# axiom_beta_shield_debug.net
KiCad netlist of a schematic drawn in EAGLE
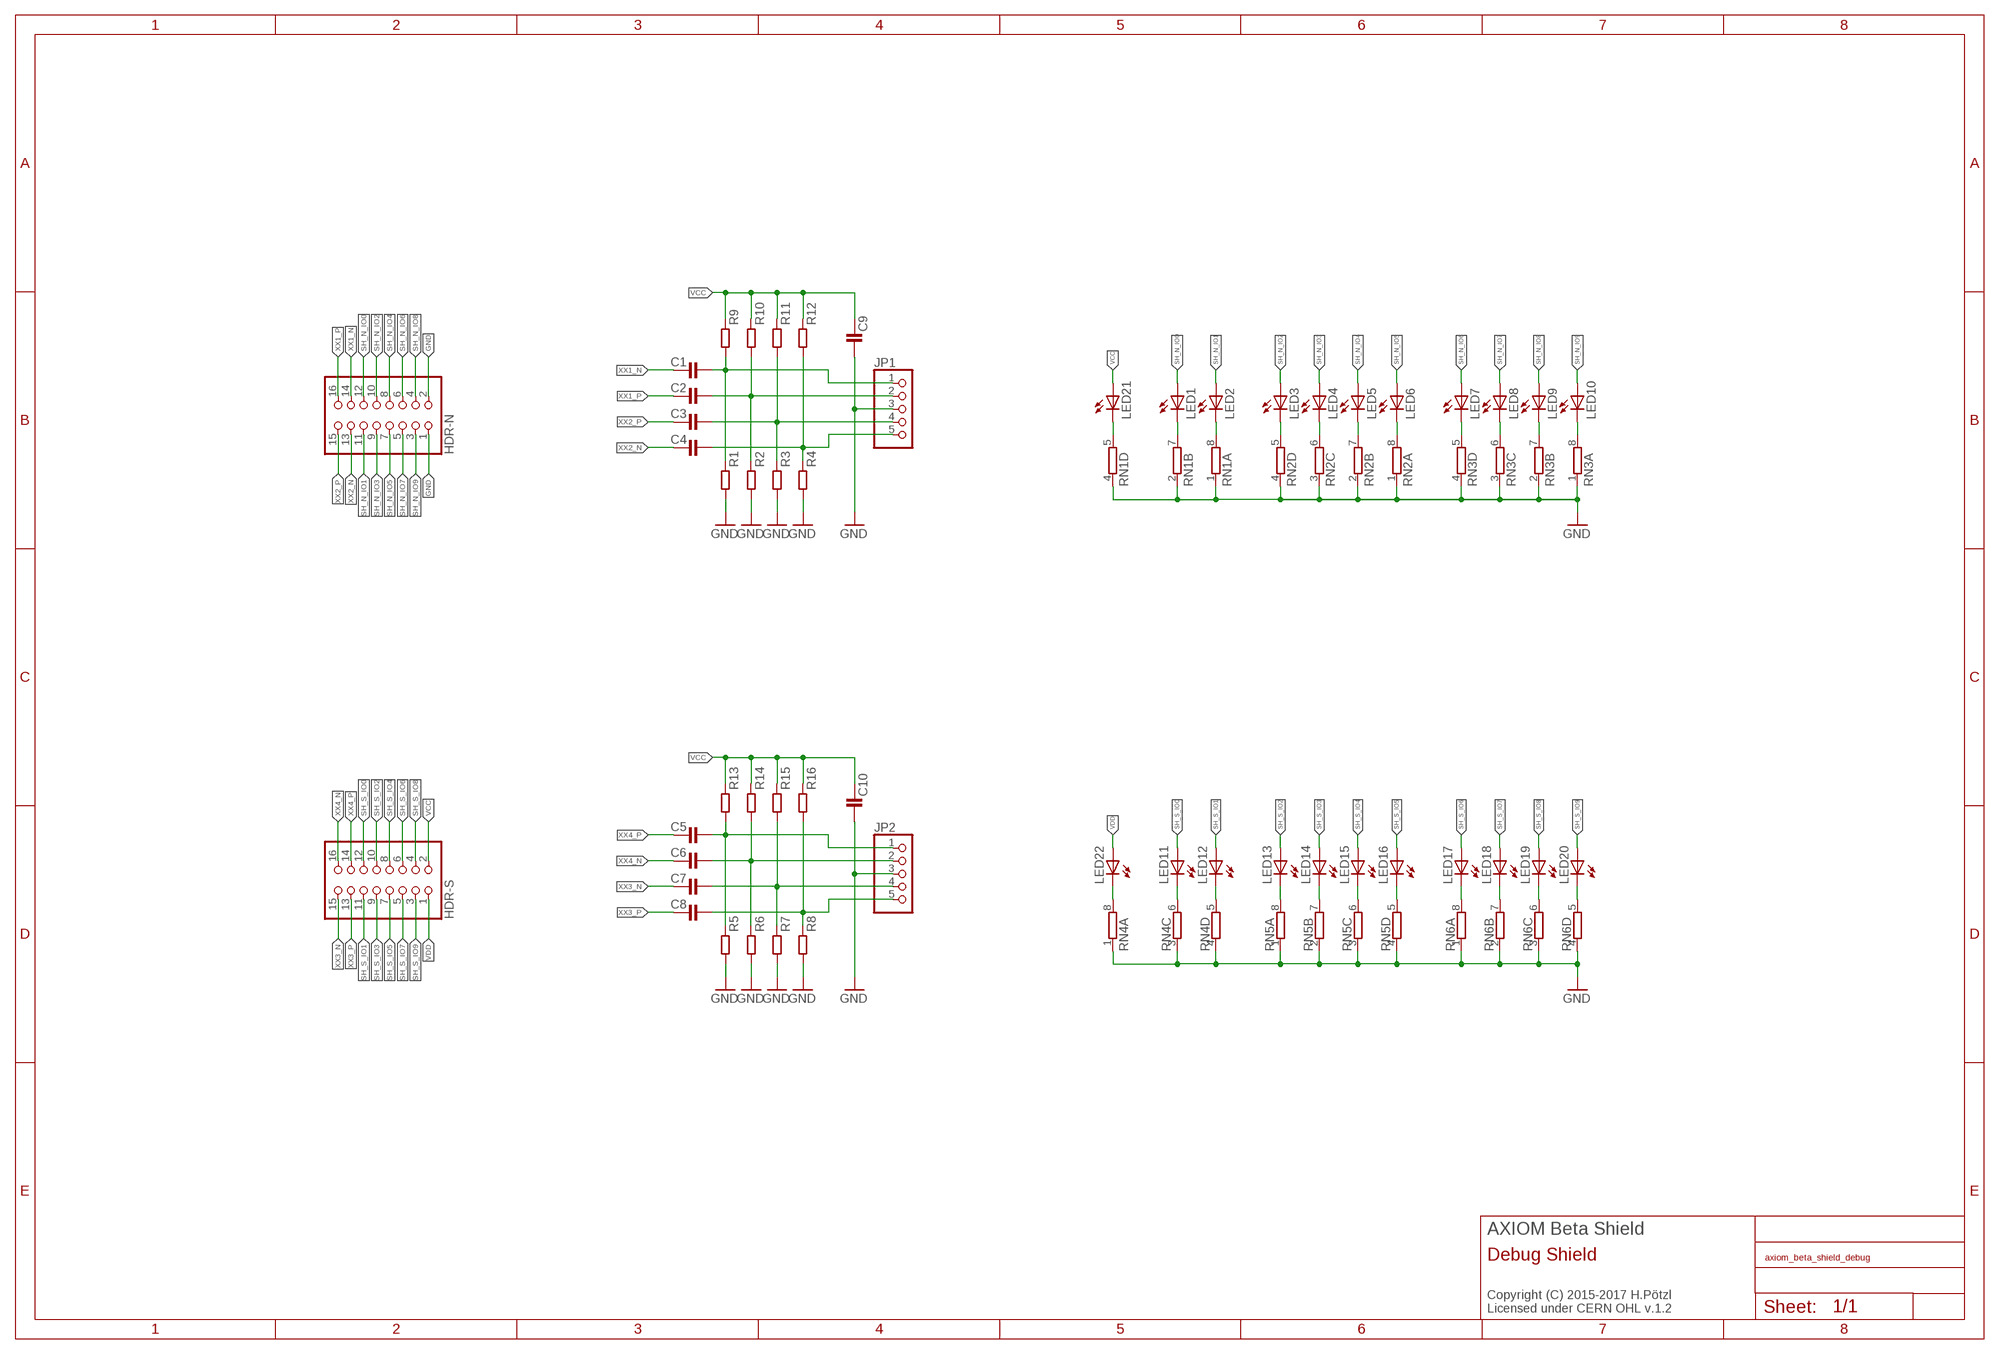
[diagram p0: schematic, sheet 1]

(export (version "E")
  (design (tool "Eeschema 10.0.6"))
  (components
    (comp (ref "C1")
      (value "C0402-C")
      (footprint "eagle-import:0402-C")
      (libsource (lib "eagle-import") (part "C0402-C"))
    )
    (comp (ref "C2")
      (value "C0402-C")
      (footprint "eagle-import:0402-C")
      (libsource (lib "eagle-import") (part "C0402-C"))
    )
    (comp (ref "C3")
      (value "C0402-C")
      (footprint "eagle-import:0402-C")
      (libsource (lib "eagle-import") (part "C0402-C"))
    )
    (comp (ref "C4")
      (value "C0402-C")
      (footprint "eagle-import:0402-C")
      (libsource (lib "eagle-import") (part "C0402-C"))
    )
    (comp (ref "C5")
      (value "C0402-C")
      (footprint "eagle-import:0402-C")
      (libsource (lib "eagle-import") (part "C0402-C"))
    )
    (comp (ref "C6")
      (value "C0402-C")
      (footprint "eagle-import:0402-C")
      (libsource (lib "eagle-import") (part "C0402-C"))
    )
    (comp (ref "C7")
      (value "C0402-C")
      (footprint "eagle-import:0402-C")
      (libsource (lib "eagle-import") (part "C0402-C"))
    )
    (comp (ref "C8")
      (value "C0402-C")
      (footprint "eagle-import:0402-C")
      (libsource (lib "eagle-import") (part "C0402-C"))
    )
    (comp (ref "C9")
      (value "C0805-C")
      (footprint "eagle-import:0805-C")
      (libsource (lib "eagle-import") (part "C0805-C"))
    )
    (comp (ref "C10")
      (value "C0805-C")
      (footprint "eagle-import:0805-C")
      (libsource (lib "eagle-import") (part "C0805-C"))
    )
    (comp (ref "HDR-N")
      (value "PINHD-2X08_2.00_SMD")
      (footprint "eagle-import:2X08M_SMD")
      (libsource (lib "eagle-import") (part "PINHD-2X08_2.00_SMD"))
    )
    (comp (ref "HDR-S")
      (value "PINHD-2X08_2.00_SMD")
      (footprint "eagle-import:2X08M_SMD")
      (libsource (lib "eagle-import") (part "PINHD-2X08_2.00_SMD"))
    )
    (comp (ref "JP1")
      (value "PINHD-1X05_1.27")
      (footprint "eagle-import:1X05U")
      (libsource (lib "eagle-import") (part "PINHD-1X05_1.27"))
    )
    (comp (ref "JP2")
      (value "PINHD-1X05_1.27")
      (footprint "eagle-import:1X05U")
      (libsource (lib "eagle-import") (part "PINHD-1X05_1.27"))
    )
    (comp (ref "LED1")
      (value "LEDCHIPLED_0603")
      (footprint "eagle-import:CHIPLED_0603")
      (libsource (lib "eagle-import") (part "LEDCHIPLED_0603"))
    )
    (comp (ref "LED2")
      (value "LEDCHIPLED_0603")
      (footprint "eagle-import:CHIPLED_0603")
      (libsource (lib "eagle-import") (part "LEDCHIPLED_0603"))
    )
    (comp (ref "LED3")
      (value "LEDCHIPLED_0603")
      (footprint "eagle-import:CHIPLED_0603")
      (libsource (lib "eagle-import") (part "LEDCHIPLED_0603"))
    )
    (comp (ref "LED4")
      (value "LEDCHIPLED_0603")
      (footprint "eagle-import:CHIPLED_0603")
      (libsource (lib "eagle-import") (part "LEDCHIPLED_0603"))
    )
    (comp (ref "LED5")
      (value "LEDCHIPLED_0603")
      (footprint "eagle-import:CHIPLED_0603")
      (libsource (lib "eagle-import") (part "LEDCHIPLED_0603"))
    )
    (comp (ref "LED6")
      (value "LEDCHIPLED_0603")
      (footprint "eagle-import:CHIPLED_0603")
      (libsource (lib "eagle-import") (part "LEDCHIPLED_0603"))
    )
    (comp (ref "LED7")
      (value "LEDCHIPLED_0603")
      (footprint "eagle-import:CHIPLED_0603")
      (libsource (lib "eagle-import") (part "LEDCHIPLED_0603"))
    )
    (comp (ref "LED8")
      (value "LEDCHIPLED_0603")
      (footprint "eagle-import:CHIPLED_0603")
      (libsource (lib "eagle-import") (part "LEDCHIPLED_0603"))
    )
    (comp (ref "LED9")
      (value "LEDCHIPLED_0603")
      (footprint "eagle-import:CHIPLED_0603")
      (libsource (lib "eagle-import") (part "LEDCHIPLED_0603"))
    )
    (comp (ref "LED10")
      (value "LEDCHIPLED_0603")
      (footprint "eagle-import:CHIPLED_0603")
      (libsource (lib "eagle-import") (part "LEDCHIPLED_0603"))
    )
    (comp (ref "LED11")
      (value "LEDCHIPLED_0603")
      (footprint "eagle-import:CHIPLED_0603")
      (libsource (lib "eagle-import") (part "LEDCHIPLED_0603"))
    )
    (comp (ref "LED12")
      (value "LEDCHIPLED_0603")
      (footprint "eagle-import:CHIPLED_0603")
      (libsource (lib "eagle-import") (part "LEDCHIPLED_0603"))
    )
    (comp (ref "LED13")
      (value "LEDCHIPLED_0603")
      (footprint "eagle-import:CHIPLED_0603")
      (libsource (lib "eagle-import") (part "LEDCHIPLED_0603"))
    )
    (comp (ref "LED14")
      (value "LEDCHIPLED_0603")
      (footprint "eagle-import:CHIPLED_0603")
      (libsource (lib "eagle-import") (part "LEDCHIPLED_0603"))
    )
    (comp (ref "LED15")
      (value "LEDCHIPLED_0603")
      (footprint "eagle-import:CHIPLED_0603")
      (libsource (lib "eagle-import") (part "LEDCHIPLED_0603"))
    )
    (comp (ref "LED16")
      (value "LEDCHIPLED_0603")
      (footprint "eagle-import:CHIPLED_0603")
      (libsource (lib "eagle-import") (part "LEDCHIPLED_0603"))
    )
    (comp (ref "LED17")
      (value "LEDCHIPLED_0603")
      (footprint "eagle-import:CHIPLED_0603")
      (libsource (lib "eagle-import") (part "LEDCHIPLED_0603"))
    )
    (comp (ref "LED18")
      (value "LEDCHIPLED_0603")
      (footprint "eagle-import:CHIPLED_0603")
      (libsource (lib "eagle-import") (part "LEDCHIPLED_0603"))
    )
    (comp (ref "LED19")
      (value "LEDCHIPLED_0603")
      (footprint "eagle-import:CHIPLED_0603")
      (libsource (lib "eagle-import") (part "LEDCHIPLED_0603"))
    )
    (comp (ref "LED20")
      (value "LEDCHIPLED_0603")
      (footprint "eagle-import:CHIPLED_0603")
      (libsource (lib "eagle-import") (part "LEDCHIPLED_0603"))
    )
    (comp (ref "LED21")
      (value "LEDCHIPLED_0603")
      (footprint "eagle-import:CHIPLED_0603")
      (libsource (lib "eagle-import") (part "LEDCHIPLED_0603"))
    )
    (comp (ref "LED22")
      (value "LEDCHIPLED_0603")
      (footprint "eagle-import:CHIPLED_0603")
      (libsource (lib "eagle-import") (part "LEDCHIPLED_0603"))
    )
    (comp (ref "R1")
      (value "R0402-C")
      (footprint "eagle-import:0402-C")
      (libsource (lib "eagle-import") (part "R0402-C"))
    )
    (comp (ref "R2")
      (value "R0402-C")
      (footprint "eagle-import:0402-C")
      (libsource (lib "eagle-import") (part "R0402-C"))
    )
    (comp (ref "R3")
      (value "R0402-C")
      (footprint "eagle-import:0402-C")
      (libsource (lib "eagle-import") (part "R0402-C"))
    )
    (comp (ref "R4")
      (value "R0402-C")
      (footprint "eagle-import:0402-C")
      (libsource (lib "eagle-import") (part "R0402-C"))
    )
    (comp (ref "R5")
      (value "R0402-C")
      (footprint "eagle-import:0402-C")
      (libsource (lib "eagle-import") (part "R0402-C"))
    )
    (comp (ref "R6")
      (value "R0402-C")
      (footprint "eagle-import:0402-C")
      (libsource (lib "eagle-import") (part "R0402-C"))
    )
    (comp (ref "R7")
      (value "R0402-C")
      (footprint "eagle-import:0402-C")
      (libsource (lib "eagle-import") (part "R0402-C"))
    )
    (comp (ref "R8")
      (value "R0402-C")
      (footprint "eagle-import:0402-C")
      (libsource (lib "eagle-import") (part "R0402-C"))
    )
    (comp (ref "R9")
      (value "R0402-C")
      (footprint "eagle-import:0402-C")
      (libsource (lib "eagle-import") (part "R0402-C"))
    )
    (comp (ref "R10")
      (value "R0402-C")
      (footprint "eagle-import:0402-C")
      (libsource (lib "eagle-import") (part "R0402-C"))
    )
    (comp (ref "R11")
      (value "R0402-C")
      (footprint "eagle-import:0402-C")
      (libsource (lib "eagle-import") (part "R0402-C"))
    )
    (comp (ref "R12")
      (value "R0402-C")
      (footprint "eagle-import:0402-C")
      (libsource (lib "eagle-import") (part "R0402-C"))
    )
    (comp (ref "R13")
      (value "R0402-C")
      (footprint "eagle-import:0402-C")
      (libsource (lib "eagle-import") (part "R0402-C"))
    )
    (comp (ref "R14")
      (value "R0402-C")
      (footprint "eagle-import:0402-C")
      (libsource (lib "eagle-import") (part "R0402-C"))
    )
    (comp (ref "R15")
      (value "R0402-C")
      (footprint "eagle-import:0402-C")
      (libsource (lib "eagle-import") (part "R0402-C"))
    )
    (comp (ref "R16")
      (value "R0402-C")
      (footprint "eagle-import:0402-C")
      (libsource (lib "eagle-import") (part "R0402-C"))
    )
    (comp (ref "RN1")
      (value "4R-NCAY16")
      (footprint "eagle-import:CAY16")
      (libsource (lib "eagle-import") (part "4R-NCAY16"))
    )
    (comp (ref "RN2")
      (value "4R-NCAY16")
      (footprint "eagle-import:CAY16")
      (libsource (lib "eagle-import") (part "4R-NCAY16"))
    )
    (comp (ref "RN3")
      (value "4R-NCAY16")
      (footprint "eagle-import:CAY16")
      (libsource (lib "eagle-import") (part "4R-NCAY16"))
    )
    (comp (ref "RN4")
      (value "4R-NCAY16")
      (footprint "eagle-import:CAY16")
      (libsource (lib "eagle-import") (part "4R-NCAY16"))
    )
    (comp (ref "RN5")
      (value "4R-NCAY16")
      (footprint "eagle-import:CAY16")
      (libsource (lib "eagle-import") (part "4R-NCAY16"))
    )
    (comp (ref "RN6")
      (value "4R-NCAY16")
      (footprint "eagle-import:CAY16")
      (libsource (lib "eagle-import") (part "4R-NCAY16"))
    )
  )
  (nets
    (net (code "1") (name "GND") (class "Default")
      (node (ref "C10") (pin "2") (pinfunction "2_2") (pintype "passive"))
      (node (ref "C9") (pin "2") (pinfunction "2_2") (pintype "passive"))
      (node (ref "HDR-N") (pin "1") (pinfunction "1_1") (pintype "passive"))
      (node (ref "HDR-N") (pin "2") (pinfunction "2_2") (pintype "passive"))
      (node (ref "JP1") (pin "3") (pinfunction "3_3") (pintype "passive"))
      (node (ref "JP2") (pin "3") (pinfunction "3_3") (pintype "passive"))
      (node (ref "R1") (pin "2") (pinfunction "2_2") (pintype "passive"))
      (node (ref "R2") (pin "2") (pinfunction "2_2") (pintype "passive"))
      (node (ref "R3") (pin "2") (pinfunction "2_2") (pintype "passive"))
      (node (ref "R4") (pin "2") (pinfunction "2_2") (pintype "passive"))
      (node (ref "R5") (pin "2") (pinfunction "2_2") (pintype "passive"))
      (node (ref "R6") (pin "2") (pinfunction "2_2") (pintype "passive"))
      (node (ref "R7") (pin "2") (pinfunction "2_2") (pintype "passive"))
      (node (ref "R8") (pin "2") (pinfunction "2_2") (pintype "passive"))
      (node (ref "RN1") (pin "1") (pinfunction "1_1") (pintype "passive"))
      (node (ref "RN1") (pin "2") (pinfunction "1_2") (pintype "passive"))
      (node (ref "RN1") (pin "4") (pinfunction "1_4") (pintype "passive"))
      (node (ref "RN2") (pin "1") (pinfunction "1_1") (pintype "passive"))
      (node (ref "RN2") (pin "2") (pinfunction "1_2") (pintype "passive"))
      (node (ref "RN2") (pin "3") (pinfunction "1_3") (pintype "passive"))
      (node (ref "RN2") (pin "4") (pinfunction "1_4") (pintype "passive"))
      (node (ref "RN3") (pin "1") (pinfunction "1_1") (pintype "passive"))
      (node (ref "RN3") (pin "2") (pinfunction "1_2") (pintype "passive"))
      (node (ref "RN3") (pin "3") (pinfunction "1_3") (pintype "passive"))
      (node (ref "RN3") (pin "4") (pinfunction "1_4") (pintype "passive"))
      (node (ref "RN4") (pin "1") (pinfunction "1_1") (pintype "passive"))
      (node (ref "RN4") (pin "3") (pinfunction "1_3") (pintype "passive"))
      (node (ref "RN4") (pin "4") (pinfunction "1_4") (pintype "passive"))
      (node (ref "RN5") (pin "1") (pinfunction "1_1") (pintype "passive"))
      (node (ref "RN5") (pin "2") (pinfunction "1_2") (pintype "passive"))
      (node (ref "RN5") (pin "3") (pinfunction "1_3") (pintype "passive"))
      (node (ref "RN5") (pin "4") (pinfunction "1_4") (pintype "passive"))
      (node (ref "RN6") (pin "1") (pinfunction "1_1") (pintype "passive"))
      (node (ref "RN6") (pin "2") (pinfunction "1_2") (pintype "passive"))
      (node (ref "RN6") (pin "3") (pinfunction "1_3") (pintype "passive"))
      (node (ref "RN6") (pin "4") (pinfunction "1_4") (pintype "passive"))
    )
    (net (code "2") (name "Net-(C1-Pad2)") (class "Default")
      (node (ref "C1") (pin "2") (pinfunction "2_2") (pintype "passive"))
      (node (ref "JP1") (pin "1") (pinfunction "1_1") (pintype "passive"))
      (node (ref "R1") (pin "1") (pinfunction "1_1") (pintype "passive"))
      (node (ref "R9") (pin "2") (pinfunction "2_2") (pintype "passive"))
    )
    (net (code "3") (name "Net-(C2-Pad2)") (class "Default")
      (node (ref "C2") (pin "2") (pinfunction "2_2") (pintype "passive"))
      (node (ref "JP1") (pin "2") (pinfunction "2_2") (pintype "passive"))
      (node (ref "R10") (pin "2") (pinfunction "2_2") (pintype "passive"))
      (node (ref "R2") (pin "1") (pinfunction "1_1") (pintype "passive"))
    )
    (net (code "4") (name "Net-(C3-Pad2)") (class "Default")
      (node (ref "C3") (pin "2") (pinfunction "2_2") (pintype "passive"))
      (node (ref "JP1") (pin "4") (pinfunction "4_4") (pintype "passive"))
      (node (ref "R11") (pin "2") (pinfunction "2_2") (pintype "passive"))
      (node (ref "R3") (pin "1") (pinfunction "1_1") (pintype "passive"))
    )
    (net (code "5") (name "Net-(C4-Pad2)") (class "Default")
      (node (ref "C4") (pin "2") (pinfunction "2_2") (pintype "passive"))
      (node (ref "JP1") (pin "5") (pinfunction "5_5") (pintype "passive"))
      (node (ref "R12") (pin "2") (pinfunction "2_2") (pintype "passive"))
      (node (ref "R4") (pin "1") (pinfunction "1_1") (pintype "passive"))
    )
    (net (code "6") (name "Net-(C5-Pad2)") (class "Default")
      (node (ref "C5") (pin "2") (pinfunction "2_2") (pintype "passive"))
      (node (ref "JP2") (pin "1") (pinfunction "1_1") (pintype "passive"))
      (node (ref "R13") (pin "2") (pinfunction "2_2") (pintype "passive"))
      (node (ref "R5") (pin "1") (pinfunction "1_1") (pintype "passive"))
    )
    (net (code "7") (name "Net-(C6-Pad2)") (class "Default")
      (node (ref "C6") (pin "2") (pinfunction "2_2") (pintype "passive"))
      (node (ref "JP2") (pin "2") (pinfunction "2_2") (pintype "passive"))
      (node (ref "R14") (pin "2") (pinfunction "2_2") (pintype "passive"))
      (node (ref "R6") (pin "1") (pinfunction "1_1") (pintype "passive"))
    )
    (net (code "8") (name "Net-(C7-Pad2)") (class "Default")
      (node (ref "C7") (pin "2") (pinfunction "2_2") (pintype "passive"))
      (node (ref "JP2") (pin "4") (pinfunction "4_4") (pintype "passive"))
      (node (ref "R15") (pin "2") (pinfunction "2_2") (pintype "passive"))
      (node (ref "R7") (pin "1") (pinfunction "1_1") (pintype "passive"))
    )
    (net (code "9") (name "Net-(C8-Pad2)") (class "Default")
      (node (ref "C8") (pin "2") (pinfunction "2_2") (pintype "passive"))
      (node (ref "JP2") (pin "5") (pinfunction "5_5") (pintype "passive"))
      (node (ref "R16") (pin "2") (pinfunction "2_2") (pintype "passive"))
      (node (ref "R8") (pin "1") (pinfunction "1_1") (pintype "passive"))
    )
    (net (code "10") (name "Net-(RN1A-2)") (class "Default")
      (node (ref "LED2") (pin "C") (pinfunction "C_C") (pintype "passive"))
      (node (ref "RN1") (pin "8") (pinfunction "2_8") (pintype "passive"))
    )
    (net (code "11") (name "Net-(RN1B-2)") (class "Default")
      (node (ref "LED1") (pin "C") (pinfunction "C_C") (pintype "passive"))
      (node (ref "RN1") (pin "7") (pinfunction "2_7") (pintype "passive"))
    )
    (net (code "12") (name "Net-(RN1D-2)") (class "Default")
      (node (ref "LED21") (pin "C") (pinfunction "C_C") (pintype "passive"))
      (node (ref "RN1") (pin "5") (pinfunction "2_5") (pintype "passive"))
    )
    (net (code "13") (name "Net-(RN2A-2)") (class "Default")
      (node (ref "LED6") (pin "C") (pinfunction "C_C") (pintype "passive"))
      (node (ref "RN2") (pin "8") (pinfunction "2_8") (pintype "passive"))
    )
    (net (code "14") (name "Net-(RN2B-2)") (class "Default")
      (node (ref "LED5") (pin "C") (pinfunction "C_C") (pintype "passive"))
      (node (ref "RN2") (pin "7") (pinfunction "2_7") (pintype "passive"))
    )
    (net (code "15") (name "Net-(RN2C-2)") (class "Default")
      (node (ref "LED4") (pin "C") (pinfunction "C_C") (pintype "passive"))
      (node (ref "RN2") (pin "6") (pinfunction "2_6") (pintype "passive"))
    )
    (net (code "16") (name "Net-(RN2D-2)") (class "Default")
      (node (ref "LED3") (pin "C") (pinfunction "C_C") (pintype "passive"))
      (node (ref "RN2") (pin "5") (pinfunction "2_5") (pintype "passive"))
    )
    (net (code "17") (name "Net-(RN3A-2)") (class "Default")
      (node (ref "LED10") (pin "C") (pinfunction "C_C") (pintype "passive"))
      (node (ref "RN3") (pin "8") (pinfunction "2_8") (pintype "passive"))
    )
    (net (code "18") (name "Net-(RN3B-2)") (class "Default")
      (node (ref "LED9") (pin "C") (pinfunction "C_C") (pintype "passive"))
      (node (ref "RN3") (pin "7") (pinfunction "2_7") (pintype "passive"))
    )
    (net (code "19") (name "Net-(RN3C-2)") (class "Default")
      (node (ref "LED8") (pin "C") (pinfunction "C_C") (pintype "passive"))
      (node (ref "RN3") (pin "6") (pinfunction "2_6") (pintype "passive"))
    )
    (net (code "20") (name "Net-(RN3D-2)") (class "Default")
      (node (ref "LED7") (pin "C") (pinfunction "C_C") (pintype "passive"))
      (node (ref "RN3") (pin "5") (pinfunction "2_5") (pintype "passive"))
    )
    (net (code "21") (name "Net-(RN4A-2)") (class "Default")
      (node (ref "LED22") (pin "C") (pinfunction "C_C") (pintype "passive"))
      (node (ref "RN4") (pin "8") (pinfunction "2_8") (pintype "passive"))
    )
    (net (code "22") (name "Net-(RN4C-2)") (class "Default")
      (node (ref "LED11") (pin "C") (pinfunction "C_C") (pintype "passive"))
      (node (ref "RN4") (pin "6") (pinfunction "2_6") (pintype "passive"))
    )
    (net (code "23") (name "Net-(RN4D-2)") (class "Default")
      (node (ref "LED12") (pin "C") (pinfunction "C_C") (pintype "passive"))
      (node (ref "RN4") (pin "5") (pinfunction "2_5") (pintype "passive"))
    )
    (net (code "24") (name "Net-(RN5A-2)") (class "Default")
      (node (ref "LED13") (pin "C") (pinfunction "C_C") (pintype "passive"))
      (node (ref "RN5") (pin "8") (pinfunction "2_8") (pintype "passive"))
    )
    (net (code "25") (name "Net-(RN5B-2)") (class "Default")
      (node (ref "LED14") (pin "C") (pinfunction "C_C") (pintype "passive"))
      (node (ref "RN5") (pin "7") (pinfunction "2_7") (pintype "passive"))
    )
    (net (code "26") (name "Net-(RN5C-2)") (class "Default")
      (node (ref "LED15") (pin "C") (pinfunction "C_C") (pintype "passive"))
      (node (ref "RN5") (pin "6") (pinfunction "2_6") (pintype "passive"))
    )
    (net (code "27") (name "Net-(RN5D-2)") (class "Default")
      (node (ref "LED16") (pin "C") (pinfunction "C_C") (pintype "passive"))
      (node (ref "RN5") (pin "5") (pinfunction "2_5") (pintype "passive"))
    )
    (net (code "28") (name "Net-(RN6A-2)") (class "Default")
      (node (ref "LED17") (pin "C") (pinfunction "C_C") (pintype "passive"))
      (node (ref "RN6") (pin "8") (pinfunction "2_8") (pintype "passive"))
    )
    (net (code "29") (name "Net-(RN6B-2)") (class "Default")
      (node (ref "LED18") (pin "C") (pinfunction "C_C") (pintype "passive"))
      (node (ref "RN6") (pin "7") (pinfunction "2_7") (pintype "passive"))
    )
    (net (code "30") (name "Net-(RN6C-2)") (class "Default")
      (node (ref "LED19") (pin "C") (pinfunction "C_C") (pintype "passive"))
      (node (ref "RN6") (pin "6") (pinfunction "2_6") (pintype "passive"))
    )
    (net (code "31") (name "Net-(RN6D-2)") (class "Default")
      (node (ref "LED20") (pin "C") (pinfunction "C_C") (pintype "passive"))
      (node (ref "RN6") (pin "5") (pinfunction "2_5") (pintype "passive"))
    )
    (net (code "32") (name "SH_N_IO0") (class "Default")
      (node (ref "HDR-N") (pin "12") (pinfunction "12_12") (pintype "passive"))
      (node (ref "LED1") (pin "A") (pinfunction "A_A") (pintype "passive"))
    )
    (net (code "33") (name "SH_N_IO1") (class "Default")
      (node (ref "HDR-N") (pin "11") (pinfunction "11_11") (pintype "passive"))
      (node (ref "LED2") (pin "A") (pinfunction "A_A") (pintype "passive"))
    )
    (net (code "34") (name "SH_N_IO2") (class "Default")
      (node (ref "HDR-N") (pin "10") (pinfunction "10_10") (pintype "passive"))
      (node (ref "LED3") (pin "A") (pinfunction "A_A") (pintype "passive"))
    )
    (net (code "35") (name "SH_N_IO3") (class "Default")
      (node (ref "HDR-N") (pin "9") (pinfunction "9_9") (pintype "passive"))
      (node (ref "LED4") (pin "A") (pinfunction "A_A") (pintype "passive"))
    )
    (net (code "36") (name "SH_N_IO4") (class "Default")
      (node (ref "HDR-N") (pin "8") (pinfunction "8_8") (pintype "passive"))
      (node (ref "LED5") (pin "A") (pinfunction "A_A") (pintype "passive"))
    )
    (net (code "37") (name "SH_N_IO5") (class "Default")
      (node (ref "HDR-N") (pin "7") (pinfunction "7_7") (pintype "passive"))
      (node (ref "LED6") (pin "A") (pinfunction "A_A") (pintype "passive"))
    )
    (net (code "38") (name "SH_N_IO6") (class "Default")
      (node (ref "HDR-N") (pin "6") (pinfunction "6_6") (pintype "passive"))
      (node (ref "LED7") (pin "A") (pinfunction "A_A") (pintype "passive"))
    )
    (net (code "39") (name "SH_N_IO7") (class "Default")
      (node (ref "HDR-N") (pin "5") (pinfunction "5_5") (pintype "passive"))
      (node (ref "LED8") (pin "A") (pinfunction "A_A") (pintype "passive"))
    )
    (net (code "40") (name "SH_N_IO8") (class "Default")
      (node (ref "HDR-N") (pin "4") (pinfunction "4_4") (pintype "passive"))
      (node (ref "LED9") (pin "A") (pinfunction "A_A") (pintype "passive"))
    )
    (net (code "41") (name "SH_N_IO9") (class "Default")
      (node (ref "HDR-N") (pin "3") (pinfunction "3_3") (pintype "passive"))
      (node (ref "LED10") (pin "A") (pinfunction "A_A") (pintype "passive"))
    )
    (net (code "42") (name "SH_S_IO0") (class "Default")
      (node (ref "HDR-S") (pin "12") (pinfunction "12_12") (pintype "passive"))
      (node (ref "LED11") (pin "A") (pinfunction "A_A") (pintype "passive"))
    )
    (net (code "43") (name "SH_S_IO1") (class "Default")
      (node (ref "HDR-S") (pin "11") (pinfunction "11_11") (pintype "passive"))
      (node (ref "LED12") (pin "A") (pinfunction "A_A") (pintype "passive"))
    )
    (net (code "44") (name "SH_S_IO2") (class "Default")
      (node (ref "HDR-S") (pin "10") (pinfunction "10_10") (pintype "passive"))
      (node (ref "LED13") (pin "A") (pinfunction "A_A") (pintype "passive"))
    )
    (net (code "45") (name "SH_S_IO3") (class "Default")
      (node (ref "HDR-S") (pin "9") (pinfunction "9_9") (pintype "passive"))
      (node (ref "LED14") (pin "A") (pinfunction "A_A") (pintype "passive"))
    )
    (net (code "46") (name "SH_S_IO4") (class "Default")
      (node (ref "HDR-S") (pin "8") (pinfunction "8_8") (pintype "passive"))
      (node (ref "LED15") (pin "A") (pinfunction "A_A") (pintype "passive"))
    )
    (net (code "47") (name "SH_S_IO5") (class "Default")
      (node (ref "HDR-S") (pin "7") (pinfunction "7_7") (pintype "passive"))
      (node (ref "LED16") (pin "A") (pinfunction "A_A") (pintype "passive"))
    )
    (net (code "48") (name "SH_S_IO6") (class "Default")
      (node (ref "HDR-S") (pin "6") (pinfunction "6_6") (pintype "passive"))
      (node (ref "LED17") (pin "A") (pinfunction "A_A") (pintype "passive"))
    )
    (net (code "49") (name "SH_S_IO7") (class "Default")
      (node (ref "HDR-S") (pin "5") (pinfunction "5_5") (pintype "passive"))
      (node (ref "LED18") (pin "A") (pinfunction "A_A") (pintype "passive"))
    )
    (net (code "50") (name "SH_S_IO8") (class "Default")
      (node (ref "HDR-S") (pin "4") (pinfunction "4_4") (pintype "passive"))
      (node (ref "LED19") (pin "A") (pinfunction "A_A") (pintype "passive"))
    )
    (net (code "51") (name "SH_S_IO9") (class "Default")
      (node (ref "HDR-S") (pin "3") (pinfunction "3_3") (pintype "passive"))
      (node (ref "LED20") (pin "A") (pinfunction "A_A") (pintype "passive"))
    )
    (net (code "52") (name "VCC") (class "Default")
      (node (ref "C10") (pin "1") (pinfunction "1_1") (pintype "passive"))
      (node (ref "C9") (pin "1") (pinfunction "1_1") (pintype "passive"))
      (node (ref "HDR-S") (pin "2") (pinfunction "2_2") (pintype "passive"))
      (node (ref "LED21") (pin "A") (pinfunction "A_A") (pintype "passive"))
      (node (ref "R10") (pin "1") (pinfunction "1_1") (pintype "passive"))
      (node (ref "R11") (pin "1") (pinfunction "1_1") (pintype "passive"))
      (node (ref "R12") (pin "1") (pinfunction "1_1") (pintype "passive"))
      (node (ref "R13") (pin "1") (pinfunction "1_1") (pintype "passive"))
      (node (ref "R14") (pin "1") (pinfunction "1_1") (pintype "passive"))
      (node (ref "R15") (pin "1") (pinfunction "1_1") (pintype "passive"))
      (node (ref "R16") (pin "1") (pinfunction "1_1") (pintype "passive"))
      (node (ref "R9") (pin "1") (pinfunction "1_1") (pintype "passive"))
    )
    (net (code "53") (name "VDD") (class "Default")
      (node (ref "HDR-S") (pin "1") (pinfunction "1_1") (pintype "passive"))
      (node (ref "LED22") (pin "A") (pinfunction "A_A") (pintype "passive"))
    )
    (net (code "54") (name "XX1_N") (class "Default")
      (node (ref "C1") (pin "1") (pinfunction "1_1") (pintype "passive"))
      (node (ref "HDR-N") (pin "14") (pinfunction "14_14") (pintype "passive"))
    )
    (net (code "55") (name "XX1_P") (class "Default")
      (node (ref "C2") (pin "1") (pinfunction "1_1") (pintype "passive"))
      (node (ref "HDR-N") (pin "16") (pinfunction "16_16") (pintype "passive"))
    )
    (net (code "56") (name "XX2_N") (class "Default")
      (node (ref "C4") (pin "1") (pinfunction "1_1") (pintype "passive"))
      (node (ref "HDR-N") (pin "13") (pinfunction "13_13") (pintype "passive"))
    )
    (net (code "57") (name "XX2_P") (class "Default")
      (node (ref "C3") (pin "1") (pinfunction "1_1") (pintype "passive"))
      (node (ref "HDR-N") (pin "15") (pinfunction "15_15") (pintype "passive"))
    )
    (net (code "58") (name "XX3_N") (class "Default")
      (node (ref "C7") (pin "1") (pinfunction "1_1") (pintype "passive"))
      (node (ref "HDR-S") (pin "15") (pinfunction "15_15") (pintype "passive"))
    )
    (net (code "59") (name "XX3_P") (class "Default")
      (node (ref "C8") (pin "1") (pinfunction "1_1") (pintype "passive"))
      (node (ref "HDR-S") (pin "13") (pinfunction "13_13") (pintype "passive"))
    )
    (net (code "60") (name "XX4_N") (class "Default")
      (node (ref "C6") (pin "1") (pinfunction "1_1") (pintype "passive"))
      (node (ref "HDR-S") (pin "16") (pinfunction "16_16") (pintype "passive"))
    )
    (net (code "61") (name "XX4_P") (class "Default")
      (node (ref "C5") (pin "1") (pinfunction "1_1") (pintype "passive"))
      (node (ref "HDR-S") (pin "14") (pinfunction "14_14") (pintype "passive"))
    )
  )
)
